# 2017_FDP_PROPULSION.net
KiCad netlist of a schematic drawn in Altium Designer
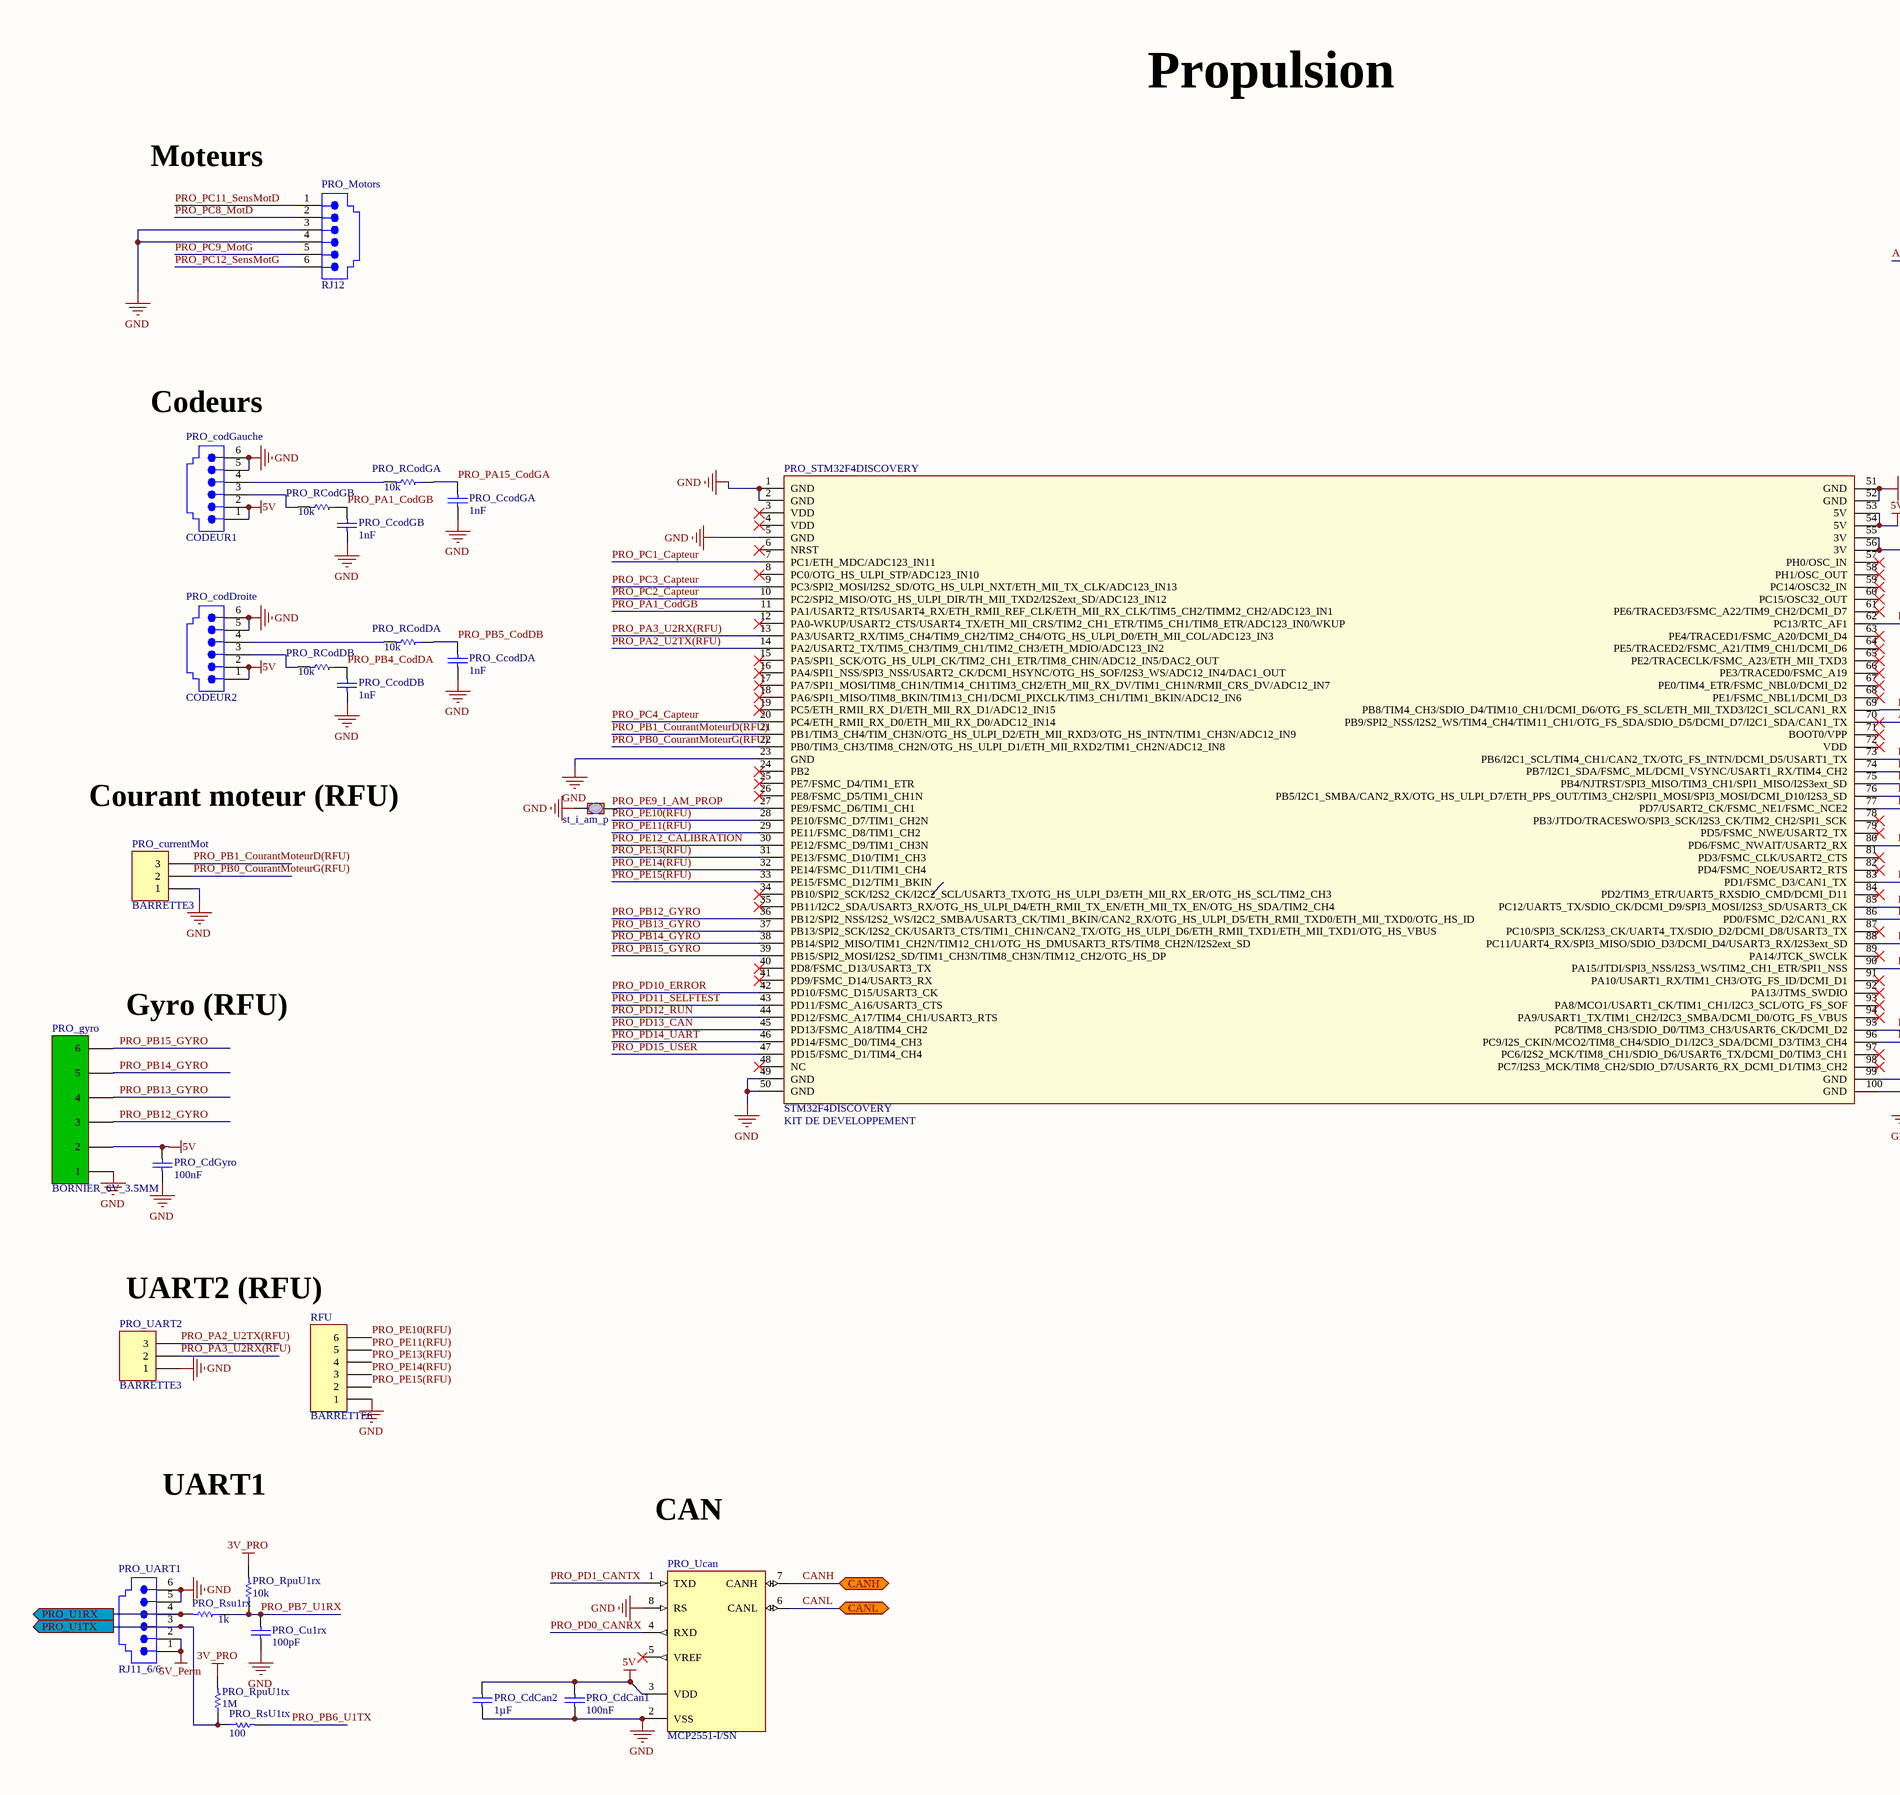
[diagram p0: 2017_FDP_PROPULSION.SchDoc, left]
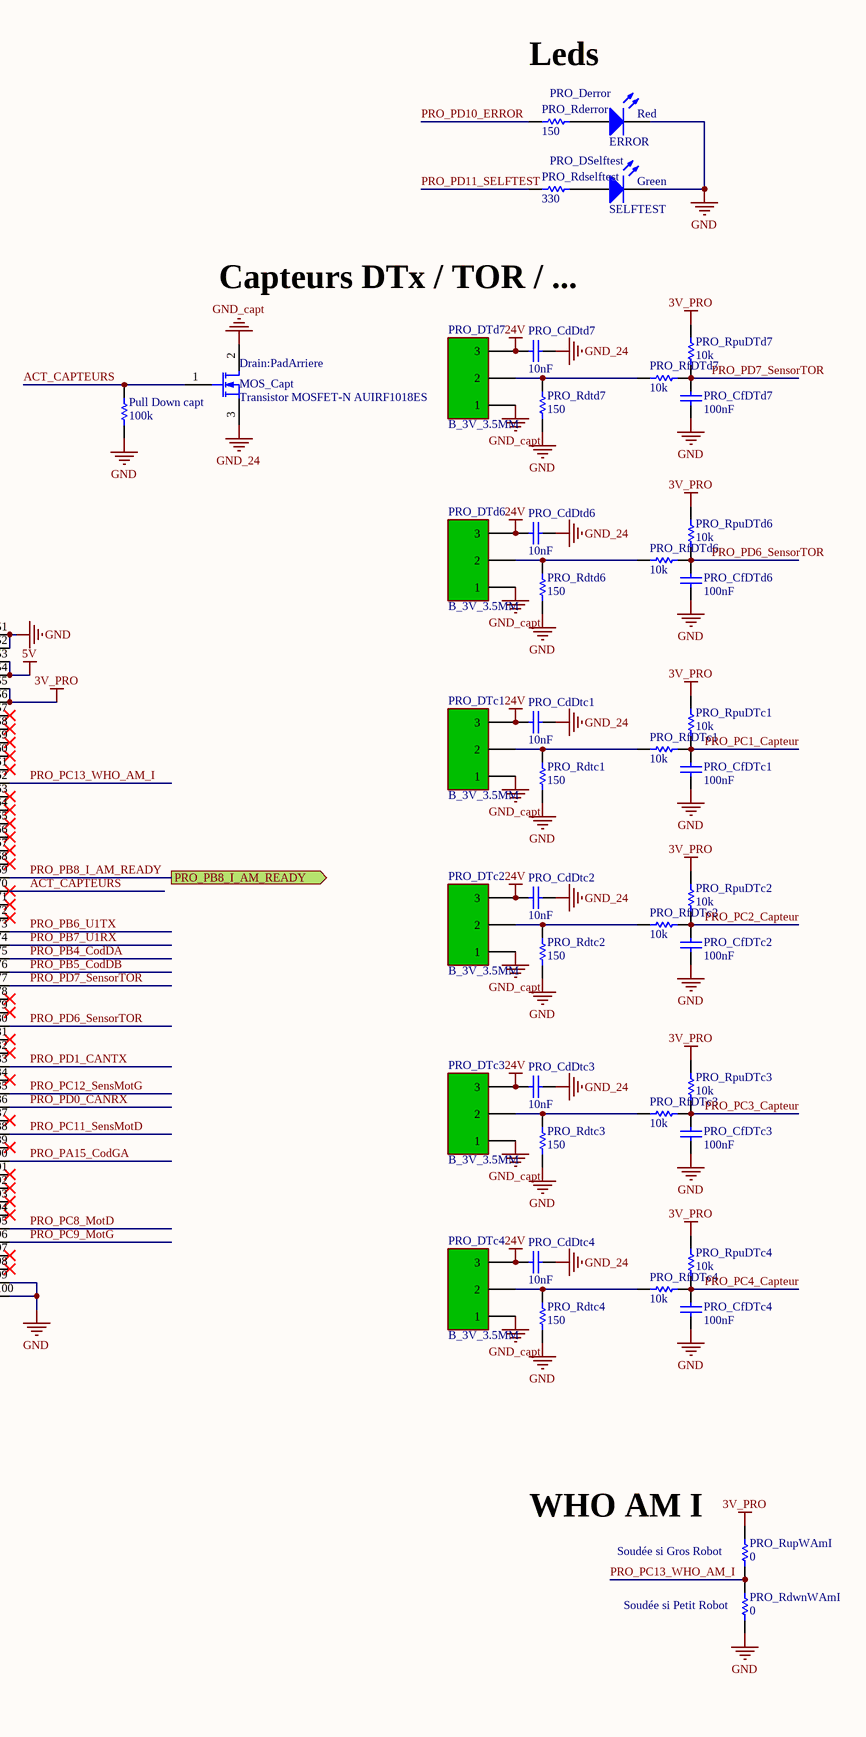
[diagram p1: 2017_FDP_PROPULSION.SchDoc, right]

(export (version "E")
  (design (tool "Eeschema 10.0.6"))
  (components
    (comp (ref "MOS_Capt")
      (value "Transistor MOSFET-N AUIRF1018ES")
      (footprint "D2PAK_GROS_PAD")
      (description "N-Channel MOSFET")
      (fields (field (name "PUBLISHER") "Altium Limited"))
      (libsource (lib "_ROBOT") (part "Transistor MOSFET-N AUIRF1018ES"))
    )
    (comp (ref "PRO_CcodDA")
      (value "1nF")
      (footprint "C0805_N")
      (description "Capacitor")
      (fields (field (name "PUBLISHER") "Altium Limited"))
      (libsource (lib "_ROBOT") (part "Condensateur"))
    )
    (comp (ref "PRO_CcodDB")
      (value "1nF")
      (footprint "C0805_N")
      (description "Capacitor")
      (fields (field (name "PUBLISHER") "Altium Limited"))
      (libsource (lib "_ROBOT") (part "Condensateur"))
    )
    (comp (ref "PRO_CcodGA")
      (value "1nF")
      (footprint "C0805_N")
      (description "Capacitor")
      (fields (field (name "PUBLISHER") "Altium Limited"))
      (libsource (lib "_ROBOT") (part "Condensateur"))
    )
    (comp (ref "PRO_CcodGB")
      (value "1nF")
      (footprint "C0805_N")
      (description "Capacitor")
      (fields (field (name "PUBLISHER") "Altium Limited"))
      (libsource (lib "_ROBOT") (part "Condensateur"))
    )
    (comp (ref "PRO_CdCan1")
      (value "100nF")
      (footprint "C0805_N")
      (description "Capacitor")
      (fields (field (name "PUBLISHER") "Altium Limited"))
      (libsource (lib "_ROBOT") (part "Condensateur"))
    )
    (comp (ref "PRO_CdCan2")
      (value "1µF")
      (footprint "C0805_N")
      (description "Capacitor")
      (fields (field (name "PUBLISHER") "Altium Limited"))
      (libsource (lib "_ROBOT") (part "Condensateur"))
    )
    (comp (ref "PRO_CdDtc1")
      (value "10nF")
      (footprint "C0805_N")
      (description "Capacitor")
      (fields (field (name "PUBLISHER") "Altium Limited"))
      (libsource (lib "_ROBOT") (part "Condensateur"))
    )
    (comp (ref "PRO_CdDtc2")
      (value "10nF")
      (footprint "C0805_N")
      (description "Capacitor")
      (fields (field (name "PUBLISHER") "Altium Limited"))
      (libsource (lib "_ROBOT") (part "Condensateur"))
    )
    (comp (ref "PRO_CdDtc3")
      (value "10nF")
      (footprint "C0805_N")
      (description "Capacitor")
      (fields (field (name "PUBLISHER") "Altium Limited"))
      (libsource (lib "_ROBOT") (part "Condensateur"))
    )
    (comp (ref "PRO_CdDtc4")
      (value "10nF")
      (footprint "C0805_N")
      (description "Capacitor")
      (fields (field (name "PUBLISHER") "Altium Limited"))
      (libsource (lib "_ROBOT") (part "Condensateur"))
    )
    (comp (ref "PRO_CdDtd6")
      (value "10nF")
      (footprint "C0805_N")
      (description "Capacitor")
      (fields (field (name "PUBLISHER") "Altium Limited"))
      (libsource (lib "_ROBOT") (part "Condensateur"))
    )
    (comp (ref "PRO_CdDtd7")
      (value "10nF")
      (footprint "C0805_N")
      (description "Capacitor")
      (fields (field (name "PUBLISHER") "Altium Limited"))
      (libsource (lib "_ROBOT") (part "Condensateur"))
    )
    (comp (ref "PRO_CdGyro")
      (value "100nF")
      (footprint "C0805_N")
      (description "Capacitor")
      (fields (field (name "PUBLISHER") "Altium Limited"))
      (libsource (lib "_ROBOT") (part "Condensateur"))
    )
    (comp (ref "PRO_CfDTc1")
      (value "100nF")
      (footprint "C0805_N")
      (description "Capacitor")
      (fields (field (name "PUBLISHER") "Altium Limited"))
      (libsource (lib "_ROBOT") (part "Condensateur"))
    )
    (comp (ref "PRO_CfDTc2")
      (value "100nF")
      (footprint "C0805_N")
      (description "Capacitor")
      (fields (field (name "PUBLISHER") "Altium Limited"))
      (libsource (lib "_ROBOT") (part "Condensateur"))
    )
    (comp (ref "PRO_CfDTc3")
      (value "100nF")
      (footprint "C0805_N")
      (description "Capacitor")
      (fields (field (name "PUBLISHER") "Altium Limited"))
      (libsource (lib "_ROBOT") (part "Condensateur"))
    )
    (comp (ref "PRO_CfDTc4")
      (value "100nF")
      (footprint "C0805_N")
      (description "Capacitor")
      (fields (field (name "PUBLISHER") "Altium Limited"))
      (libsource (lib "_ROBOT") (part "Condensateur"))
    )
    (comp (ref "PRO_CfDTd6")
      (value "100nF")
      (footprint "C0805_N")
      (description "Capacitor")
      (fields (field (name "PUBLISHER") "Altium Limited"))
      (libsource (lib "_ROBOT") (part "Condensateur"))
    )
    (comp (ref "PRO_CfDTd7")
      (value "100nF")
      (footprint "C0805_N")
      (description "Capacitor")
      (fields (field (name "PUBLISHER") "Altium Limited"))
      (libsource (lib "_ROBOT") (part "Condensateur"))
    )
    (comp (ref "PRO_codDroite")
      (value "CODEUR2")
      (footprint "RJ11_6/6 - droit")
      (description "Right Angle, Standard Profile, Offset Latch DECconnect, Flangeless PCB Jack")
      (fields (field (name "PUBLISHER") "Altium Limited"))
      (libsource (lib "miniprojet") (part "RJ11_6/6"))
    )
    (comp (ref "PRO_codGauche")
      (value "CODEUR1")
      (footprint "RJ11_6/6 - droit")
      (description "Right Angle, Standard Profile, Offset Latch DECconnect, Flangeless PCB Jack")
      (fields (field (name "PUBLISHER") "Altium Limited"))
      (libsource (lib "miniprojet") (part "RJ11_6/6"))
    )
    (comp (ref "PRO_Cu1rx")
      (value "100pF")
      (footprint "C0805_N")
      (description "Capacitor")
      (fields (field (name "PUBLISHER") "Altium Limited"))
      (libsource (lib "_ROBOT") (part "Condensateur"))
    )
    (comp (ref "PRO_currentMot")
      (value "BARRETTE3")
      (footprint "HE14_3")
      (description "Header, 3-Pin")
      (fields (field (name "PUBLISHER") "Altium Limited"))
      (libsource (lib "Connecteur") (part "BARRETTE3"))
    )
    (comp (ref "PRO_Derror")
      (value "ERROR")
      (footprint "LED_0805")
      (description "Typical LED")
      (fields (field (name "PUBLISHER") "Altium Limited"))
      (libsource (lib "_ROBOT") (part "LED"))
    )
    (comp (ref "PRO_DSelftest")
      (value "SELFTEST")
      (footprint "LED_0805")
      (description "Typical LED")
      (fields (field (name "PUBLISHER") "Altium Limited"))
      (libsource (lib "_ROBOT") (part "LED"))
    )
    (comp (ref "PRO_DTc1")
      (value "B_3V_3.5MM")
      (footprint "BORNIER_3V_3.5MM")
      (libsource (lib "Connecteur") (part "BORNIER_3V_3.5MM"))
    )
    (comp (ref "PRO_DTc2")
      (value "B_3V_3.5MM")
      (footprint "BORNIER_3V_3.5MM")
      (libsource (lib "Connecteur") (part "BORNIER_3V_3.5MM"))
    )
    (comp (ref "PRO_DTc3")
      (value "B_3V_3.5MM")
      (footprint "BORNIER_3V_3.5MM")
      (libsource (lib "Connecteur") (part "BORNIER_3V_3.5MM"))
    )
    (comp (ref "PRO_DTc4")
      (value "B_3V_3.5MM")
      (footprint "BORNIER_3V_3.5MM")
      (libsource (lib "Connecteur") (part "BORNIER_3V_3.5MM"))
    )
    (comp (ref "PRO_DTd6")
      (value "B_3V_3.5MM")
      (footprint "BORNIER_3V_3.5MM")
      (libsource (lib "Connecteur") (part "BORNIER_3V_3.5MM"))
    )
    (comp (ref "PRO_DTd7")
      (value "B_3V_3.5MM")
      (footprint "BORNIER_3V_3.5MM")
      (libsource (lib "Connecteur") (part "BORNIER_3V_3.5MM"))
    )
    (comp (ref "PRO_gyro")
      (value "BORNIER_6V_3.5MM")
      (footprint "BORNIER_6V_3.5MM")
      (libsource (lib "Connecteur") (part "BORNIER_6V_3.5MM"))
    )
    (comp (ref "PRO_Motors")
      (value "RJ12")
      (footprint "RJ11_6/6 - droit")
      (description "Right Angle, Standard Profile, Offset Latch DECconnect, Flangeless PCB Jack")
      (fields (field (name "PUBLISHER") "Altium Limited"))
      (libsource (lib "Connecteur") (part "RJ11_6/6"))
    )
    (comp (ref "PRO_RCodDA")
      (value "10k")
      (footprint "R1206_N")
      (description "Resistor")
      (fields (field (name "PUBLISHER") "Altium Limited"))
      (libsource (lib "_ROBOT") (part "Resistor"))
    )
    (comp (ref "PRO_RCodDB")
      (value "10k")
      (footprint "R1206_N")
      (description "Resistor")
      (fields (field (name "PUBLISHER") "Altium Limited"))
      (libsource (lib "_ROBOT") (part "Resistor"))
    )
    (comp (ref "PRO_RCodGA")
      (value "10k")
      (footprint "R1206_N")
      (description "Resistor")
      (fields (field (name "PUBLISHER") "Altium Limited"))
      (libsource (lib "_ROBOT") (part "Resistor"))
    )
    (comp (ref "PRO_RCodGB")
      (value "10k")
      (footprint "R1206_N")
      (description "Resistor")
      (fields (field (name "PUBLISHER") "Altium Limited"))
      (libsource (lib "_ROBOT") (part "Resistor"))
    )
    (comp (ref "PRO_Rderror")
      (value "150")
      (footprint "R1206_N")
      (description "Resistor")
      (fields (field (name "PUBLISHER") "Altium Limited"))
      (libsource (lib "_ROBOT") (part "Resistor"))
    )
    (comp (ref "PRO_Rdselftest")
      (value "330")
      (footprint "R1206_N")
      (description "Resistor")
      (fields (field (name "PUBLISHER") "Altium Limited"))
      (libsource (lib "_ROBOT") (part "Resistor"))
    )
    (comp (ref "PRO_Rdtc1")
      (value "150")
      (footprint "R1206_N")
      (description "Resistor")
      (fields (field (name "PUBLISHER") "Altium Limited"))
      (libsource (lib "_ROBOT") (part "Resistor"))
    )
    (comp (ref "PRO_Rdtc2")
      (value "150")
      (footprint "R1206_N")
      (description "Resistor")
      (fields (field (name "PUBLISHER") "Altium Limited"))
      (libsource (lib "_ROBOT") (part "Resistor"))
    )
    (comp (ref "PRO_Rdtc3")
      (value "150")
      (footprint "R1206_N")
      (description "Resistor")
      (fields (field (name "PUBLISHER") "Altium Limited"))
      (libsource (lib "_ROBOT") (part "Resistor"))
    )
    (comp (ref "PRO_Rdtc4")
      (value "150")
      (footprint "R1206_N")
      (description "Resistor")
      (fields (field (name "PUBLISHER") "Altium Limited"))
      (libsource (lib "_ROBOT") (part "Resistor"))
    )
    (comp (ref "PRO_Rdtd6")
      (value "150")
      (footprint "R1206_N")
      (description "Resistor")
      (fields (field (name "PUBLISHER") "Altium Limited"))
      (libsource (lib "_ROBOT") (part "Resistor"))
    )
    (comp (ref "PRO_Rdtd7")
      (value "150")
      (footprint "R1206_N")
      (description "Resistor")
      (fields (field (name "PUBLISHER") "Altium Limited"))
      (libsource (lib "_ROBOT") (part "Resistor"))
    )
    (comp (ref "PRO_RdwnWAmI")
      (value "0")
      (footprint "R1206_N")
      (description "Resistor")
      (fields (field (name "PUBLISHER") "Altium Limited"))
      (libsource (lib "_ROBOT") (part "Resistor"))
    )
    (comp (ref "PRO_RfDTc1")
      (value "10k")
      (footprint "R1206_N")
      (description "Resistor")
      (fields (field (name "PUBLISHER") "Altium Limited"))
      (libsource (lib "_ROBOT") (part "Resistor"))
    )
    (comp (ref "PRO_RfDTc2")
      (value "10k")
      (footprint "R1206_N")
      (description "Resistor")
      (fields (field (name "PUBLISHER") "Altium Limited"))
      (libsource (lib "_ROBOT") (part "Resistor"))
    )
    (comp (ref "PRO_RfDTc3")
      (value "10k")
      (footprint "R1206_N")
      (description "Resistor")
      (fields (field (name "PUBLISHER") "Altium Limited"))
      (libsource (lib "_ROBOT") (part "Resistor"))
    )
    (comp (ref "PRO_RfDTc4")
      (value "10k")
      (footprint "R1206_N")
      (description "Resistor")
      (fields (field (name "PUBLISHER") "Altium Limited"))
      (libsource (lib "_ROBOT") (part "Resistor"))
    )
    (comp (ref "PRO_RfDTd6")
      (value "10k")
      (footprint "R1206_N")
      (description "Resistor")
      (fields (field (name "PUBLISHER") "Altium Limited"))
      (libsource (lib "_ROBOT") (part "Resistor"))
    )
    (comp (ref "PRO_RfDTd7")
      (value "10k")
      (footprint "R1206_N")
      (description "Resistor")
      (fields (field (name "PUBLISHER") "Altium Limited"))
      (libsource (lib "_ROBOT") (part "Resistor"))
    )
    (comp (ref "PRO_RpuDTc1")
      (value "10k")
      (footprint "R1206_N")
      (description "Resistor")
      (fields (field (name "PUBLISHER") "Altium Limited"))
      (libsource (lib "_ROBOT") (part "Resistor"))
    )
    (comp (ref "PRO_RpuDTc2")
      (value "10k")
      (footprint "R1206_N")
      (description "Resistor")
      (fields (field (name "PUBLISHER") "Altium Limited"))
      (libsource (lib "_ROBOT") (part "Resistor"))
    )
    (comp (ref "PRO_RpuDTc3")
      (value "10k")
      (footprint "R1206_N")
      (description "Resistor")
      (fields (field (name "PUBLISHER") "Altium Limited"))
      (libsource (lib "_ROBOT") (part "Resistor"))
    )
    (comp (ref "PRO_RpuDTc4")
      (value "10k")
      (footprint "R1206_N")
      (description "Resistor")
      (fields (field (name "PUBLISHER") "Altium Limited"))
      (libsource (lib "_ROBOT") (part "Resistor"))
    )
    (comp (ref "PRO_RpuDTd6")
      (value "10k")
      (footprint "R1206_N")
      (description "Resistor")
      (fields (field (name "PUBLISHER") "Altium Limited"))
      (libsource (lib "_ROBOT") (part "Resistor"))
    )
    (comp (ref "PRO_RpuDTd7")
      (value "10k")
      (footprint "R1206_N")
      (description "Resistor")
      (fields (field (name "PUBLISHER") "Altium Limited"))
      (libsource (lib "_ROBOT") (part "Resistor"))
    )
    (comp (ref "PRO_RpuU1rx")
      (value "10k")
      (footprint "R1206_N")
      (description "Resistor")
      (fields (field (name "PUBLISHER") "Altium Limited"))
      (libsource (lib "_ROBOT") (part "Resistor"))
    )
    (comp (ref "PRO_RpuU1tx")
      (value "1M")
      (footprint "R1206_N")
      (description "Resistor")
      (fields (field (name "PUBLISHER") "Altium Limited"))
      (libsource (lib "_ROBOT") (part "Resistor"))
    )
    (comp (ref "PRO_Rsu1rx")
      (value "1k")
      (footprint "R1206_N")
      (description "Resistor")
      (fields (field (name "PUBLISHER") "Altium Limited"))
      (libsource (lib "_ROBOT") (part "Resistor"))
    )
    (comp (ref "PRO_RsU1tx")
      (value "100")
      (footprint "R1206_N")
      (description "Resistor")
      (fields (field (name "PUBLISHER") "Altium Limited"))
      (libsource (lib "_ROBOT") (part "Resistor"))
    )
    (comp (ref "PRO_RupWAmI")
      (value "0")
      (footprint "R1206_N")
      (description "Resistor")
      (fields (field (name "PUBLISHER") "Altium Limited"))
      (libsource (lib "_ROBOT") (part "Resistor"))
    )
    (comp (ref "PRO_STM32F4DISCOVERY")
      (value "STM32F4DISCOVERY")
      (footprint "STM32_F4DISCOVERY")
      (description "KIT DE DEVELOPPEMENT POUR MICROCONTROLEUR STM32F407VGT6")
      (fields (field (name "TYPE") "KIT DE DEVELOPPEMENT"))
      (libsource (lib "circuits integres") (part "STM32F4DISCOVERY"))
    )
    (comp (ref "PRO_UART1")
      (value "RJ11_6/6")
      (footprint "RJ11_6/6 - droit")
      (description "Right Angle, Standard Profile, Offset Latch DECconnect, Flangeless PCB Jack")
      (fields (field (name "PUBLISHER") "Altium Limited"))
      (libsource (lib "Connecteur") (part "RJ11_6/6"))
    )
    (comp (ref "PRO_UART2")
      (value "BARRETTE3")
      (footprint "HE14_3")
      (description "Header, 3-Pin")
      (fields (field (name "PUBLISHER") "Altium Limited"))
      (libsource (lib "Connecteur") (part "BARRETTE3"))
    )
    (comp (ref "PRO_Ucan")
      (value "MCP2551-I/SN")
      (footprint "SO8_N")
      (description "High-Speed CAN Transceiver, 8-Pin SOIC, Industrial Temperature")
      (fields (field (name "PUBLISHER") "Damien Guitton"))
      (libsource (lib "Circuit intégré") (part "MCP2551-I/SN"))
    )
    (comp (ref "Pull Down capt")
      (value "100k")
      (footprint "R1206_N")
      (description "Resistor")
      (fields (field (name "PUBLISHER") "Altium Limited"))
      (libsource (lib "_ROBOT") (part "Resistor"))
    )
    (comp (ref "RFU")
      (value "BARRETTE6")
      (footprint "HE14_6")
      (description "Header, 6-Pin")
      (fields (field (name "PUBLISHER") "Altium Limited"))
      (libsource (lib "Connecteur") (part "BARRETTE6"))
    )
    (comp (ref "st_i_am_p")
      (value "Goutte Strap_2")
      (footprint "Goutte Strap_2 Pads_Clearance 0.254mm")
      (fields (field (name "PUBLISHER") "Damien Guitton"))
      (libsource (lib "DG_Connecteur") (part "Goutte Strap_2"))
    )
  )
  (nets
    (net (code "1") (name "/ACT_CAPTEURS") (class "Default")
      (node (ref "MOS_Capt") (pin "1") (pinfunction "G_1") (pintype "passive"))
      (node (ref "PRO_STM32F4DISCOVERY") (pin "70") (pinfunction "PB9/SPI2_NSS/I2S2_WS/TIM4_CH4/TIM11_CH1/OTG_FS_SDA/SDIO_D5/DCMI_D7/I2C1_SDA/CAN1_TX_70") (pintype "passive"))
      (node (ref "Pull Down capt") (pin "2") (pinfunction "2_2") (pintype "passive"))
    )
    (net (code "2") (name "/CANH") (class "Default")
      (node (ref "PRO_Ucan") (pin "7") (pinfunction "CANH_7") (pintype "bidirectional"))
    )
    (net (code "3") (name "/CANL") (class "Default")
      (node (ref "PRO_Ucan") (pin "6") (pinfunction "CANL_6") (pintype "bidirectional"))
    )
    (net (code "4") (name "/PRO_PA1_CodGB") (class "Default")
      (node (ref "PRO_CcodGB") (pin "2") (pinfunction "2_2") (pintype "passive"))
      (node (ref "PRO_RCodGB") (pin "1") (pinfunction "1_1") (pintype "passive"))
      (node (ref "PRO_STM32F4DISCOVERY") (pin "11") (pinfunction "PA1/USART2_RTS/USART4_RX/ETH_RMII_REF_CLK/ETH_MII_RX_CLK/TIM5_CH2/TIMM2_CH2/ADC123_IN1_11") (pintype "passive"))
    )
    (net (code "5") (name "/PRO_PA2_U2TX(RFU)") (class "Default")
      (node (ref "PRO_STM32F4DISCOVERY") (pin "14") (pinfunction "PA2/USART2_TX/TIM5_CH3/TIM9_CH1/TIM2_CH3/ETH_MDIO/ADC123_IN2_14") (pintype "passive"))
      (node (ref "PRO_UART2") (pin "3") (pinfunction "3_3") (pintype "passive"))
    )
    (net (code "6") (name "/PRO_PA3_U2RX(RFU)") (class "Default")
      (node (ref "PRO_STM32F4DISCOVERY") (pin "13") (pinfunction "PA3/USART2_RX/TIM5_CH4/TIM9_CH2/TIM2_CH4/OTG_HS_ULPI_D0/ETH_MII_COL/ADC123_IN3_13") (pintype "passive"))
      (node (ref "PRO_UART2") (pin "2") (pinfunction "2_2") (pintype "passive"))
    )
    (net (code "7") (name "/PRO_PA15_CodGA") (class "Default")
      (node (ref "PRO_CcodGA") (pin "2") (pinfunction "2_2") (pintype "passive"))
      (node (ref "PRO_RCodGA") (pin "1") (pinfunction "1_1") (pintype "passive"))
      (node (ref "PRO_STM32F4DISCOVERY") (pin "90") (pinfunction "PA15/JTDI/SPI3_NSS/I2S3_WS/TIM2_CH1_ETR/SPI1_NSS_90") (pintype "passive"))
    )
    (net (code "8") (name "/PRO_PB0_CourantMoteurG(RFU)") (class "Default")
      (node (ref "PRO_STM32F4DISCOVERY") (pin "22") (pinfunction "PB0/TIM3_CH3/TIM8_CH2N/OTG_HS_ULPI_D1/ETH_MII_RXD2/TIM1_CH2N/ADC12_IN8_22") (pintype "passive"))
      (node (ref "PRO_currentMot") (pin "2") (pinfunction "2_2") (pintype "passive"))
    )
    (net (code "9") (name "/PRO_PB1_CourantMoteurD(RFU)") (class "Default")
      (node (ref "PRO_STM32F4DISCOVERY") (pin "21") (pinfunction "PB1/TIM3_CH4/TIM_CH3N/OTG_HS_ULPI_D2/ETH_MII_RXD3/OTG_HS_INTN/TIM1_CH3N/ADC12_IN9_21") (pintype "passive"))
      (node (ref "PRO_currentMot") (pin "3") (pinfunction "3_3") (pintype "passive"))
    )
    (net (code "10") (name "/PRO_PB4_CodDA") (class "Default")
      (node (ref "PRO_CcodDB") (pin "2") (pinfunction "2_2") (pintype "passive"))
      (node (ref "PRO_RCodDB") (pin "1") (pinfunction "1_1") (pintype "passive"))
      (node (ref "PRO_STM32F4DISCOVERY") (pin "75") (pinfunction "PB4/NJTRST/SPI3_MISO/TIM3_CH1/SPI1_MISO/I2S3ext_SD_75") (pintype "passive"))
    )
    (net (code "11") (name "/PRO_PB5_CodDB") (class "Default")
      (node (ref "PRO_CcodDA") (pin "2") (pinfunction "2_2") (pintype "passive"))
      (node (ref "PRO_RCodDA") (pin "1") (pinfunction "1_1") (pintype "passive"))
      (node (ref "PRO_STM32F4DISCOVERY") (pin "76") (pinfunction "PB5/I2C1_SMBA/CAN2_RX/OTG_HS_ULPI_D7/ETH_PPS_OUT/TIM3_CH2/SPI1_MOSI/SPI3_MOSI/DCMI_D10/I2S3_SD_76") (pintype "passive"))
    )
    (net (code "12") (name "/PRO_PB6_U1TX") (class "Default")
      (node (ref "PRO_RsU1tx") (pin "2") (pinfunction "2_2") (pintype "passive"))
      (node (ref "PRO_STM32F4DISCOVERY") (pin "73") (pinfunction "PB6/I2C1_SCL/TIM4_CH1/CAN2_TX/OTG_FS_INTN/DCMI_D5/USART1_TX_73") (pintype "passive"))
    )
    (net (code "13") (name "/PRO_PB7_U1RX") (class "Default")
      (node (ref "PRO_Cu1rx") (pin "2") (pinfunction "2_2") (pintype "passive"))
      (node (ref "PRO_RpuU1rx") (pin "1") (pinfunction "1_1") (pintype "passive"))
      (node (ref "PRO_Rsu1rx") (pin "1") (pinfunction "1_1") (pintype "passive"))
      (node (ref "PRO_STM32F4DISCOVERY") (pin "74") (pinfunction "PB7/I2C1_SDA/FSMC_ML/DCMI_VSYNC/USART1_RX/TIM4_CH2_74") (pintype "passive"))
    )
    (net (code "14") (name "/PRO_PB8_I_AM_READY") (class "Default")
      (node (ref "PRO_STM32F4DISCOVERY") (pin "69") (pinfunction "PB8/TIM4_CH3/SDIO_D4/TIM10_CH1/DCMI_D6/OTG_FS_SCL/ETH_MII_TXD3/I2C1_SCL/CAN1_RX_69") (pintype "passive"))
    )
    (net (code "15") (name "/PRO_PB12_GYRO") (class "Default")
      (node (ref "PRO_STM32F4DISCOVERY") (pin "36") (pinfunction "PB12/SPI2_NSS/I2S2_WS/I2C2_SMBA/USART3_CK/TIM1_BKIN/CAN2_RX/OTG_HS_ULPI_D5/ETH_RMII_TXD0/ETH_MII_TXD0/OTG_HS_ID_36") (pintype "passive"))
      (node (ref "PRO_gyro") (pin "3") (pinfunction "3_3") (pintype "passive"))
    )
    (net (code "16") (name "/PRO_PB13_GYRO") (class "Default")
      (node (ref "PRO_STM32F4DISCOVERY") (pin "37") (pinfunction "PB13/SPI2_SCK/I2S2_CK/USART3_CTS/TIM1_CH1N/CAN2_TX/OTG_HS_ULPI_D6/ETH_RMII_TXD1/ETH_MII_TXD1/OTG_HS_VBUS_37") (pintype "passive"))
      (node (ref "PRO_gyro") (pin "4") (pinfunction "4_4") (pintype "passive"))
    )
    (net (code "17") (name "/PRO_PB14_GYRO") (class "Default")
      (node (ref "PRO_STM32F4DISCOVERY") (pin "38") (pinfunction "PB14/SPI2_MISO/TIM1_CH2N/TIM12_CH1/OTG_HS_DMUSART3_RTS/TIM8_CH2N/I2S2ext_SD_38") (pintype "passive"))
      (node (ref "PRO_gyro") (pin "5") (pinfunction "5_5") (pintype "passive"))
    )
    (net (code "18") (name "/PRO_PB15_GYRO") (class "Default")
      (node (ref "PRO_STM32F4DISCOVERY") (pin "39") (pinfunction "PB15/SPI2_MOSI/I2S2_SD/TIM1_CH3N/TIM8_CH3N/TIM12_CH2/OTG_HS_DP_39") (pintype "passive"))
      (node (ref "PRO_gyro") (pin "6") (pinfunction "6_6") (pintype "passive"))
    )
    (net (code "19") (name "/PRO_PC1_Capteur") (class "Default")
      (node (ref "PRO_CfDTc1") (pin "2") (pinfunction "2_2") (pintype "passive"))
      (node (ref "PRO_RfDTc1") (pin "2") (pinfunction "2_2") (pintype "passive"))
      (node (ref "PRO_RpuDTc1") (pin "1") (pinfunction "1_1") (pintype "passive"))
      (node (ref "PRO_STM32F4DISCOVERY") (pin "7") (pinfunction "PC1/ETH_MDC/ADC123_IN11_7") (pintype "passive"))
    )
    (net (code "20") (name "/PRO_PC2_Capteur") (class "Default")
      (node (ref "PRO_CfDTc2") (pin "2") (pinfunction "2_2") (pintype "passive"))
      (node (ref "PRO_RfDTc2") (pin "2") (pinfunction "2_2") (pintype "passive"))
      (node (ref "PRO_RpuDTc2") (pin "1") (pinfunction "1_1") (pintype "passive"))
      (node (ref "PRO_STM32F4DISCOVERY") (pin "10") (pinfunction "PC2/SPI2_MISO/OTG_HS_ULPI_DIR/TH_MII_TXD2/I2S2ext_SD/ADC123_IN12_10") (pintype "passive"))
    )
    (net (code "21") (name "/PRO_PC3_Capteur") (class "Default")
      (node (ref "PRO_CfDTc3") (pin "2") (pinfunction "2_2") (pintype "passive"))
      (node (ref "PRO_RfDTc3") (pin "2") (pinfunction "2_2") (pintype "passive"))
      (node (ref "PRO_RpuDTc3") (pin "1") (pinfunction "1_1") (pintype "passive"))
      (node (ref "PRO_STM32F4DISCOVERY") (pin "9") (pinfunction "PC3/SPI2_MOSI/I2S2_SD/OTG_HS_ULPI_NXT/ETH_MII_TX_CLK/ADC123_IN13_9") (pintype "passive"))
    )
    (net (code "22") (name "/PRO_PC4_Capteur") (class "Default")
      (node (ref "PRO_CfDTc4") (pin "2") (pinfunction "2_2") (pintype "passive"))
      (node (ref "PRO_RfDTc4") (pin "2") (pinfunction "2_2") (pintype "passive"))
      (node (ref "PRO_RpuDTc4") (pin "1") (pinfunction "1_1") (pintype "passive"))
      (node (ref "PRO_STM32F4DISCOVERY") (pin "20") (pinfunction "PC4/ETH_RMII_RX_D0/ETH_MII_RX_D0/ADC12_IN14_20") (pintype "passive"))
    )
    (net (code "23") (name "/PRO_PC8_MotD") (class "Default")
      (node (ref "PRO_Motors") (pin "2") (pinfunction "2_2") (pintype "passive"))
      (node (ref "PRO_STM32F4DISCOVERY") (pin "95") (pinfunction "PC8/TIM8_CH3/SDIO_D0/TIM3_CH3/USART6_CK/DCMI_D2_95") (pintype "passive"))
    )
    (net (code "24") (name "/PRO_PC9_MotG") (class "Default")
      (node (ref "PRO_Motors") (pin "5") (pinfunction "5_5") (pintype "passive"))
      (node (ref "PRO_STM32F4DISCOVERY") (pin "96") (pinfunction "PC9/I2S_CKIN/MCO2/TIM8_CH4/SDIO_D1/I2C3_SDA/DCMI_D3/TIM3_CH4_96") (pintype "passive"))
    )
    (net (code "25") (name "/PRO_PC11_SensMotD") (class "Default")
      (node (ref "PRO_Motors") (pin "1") (pinfunction "1_1") (pintype "passive"))
      (node (ref "PRO_STM32F4DISCOVERY") (pin "88") (pinfunction "PC11/UART4_RX/SPI3_MISO/SDIO_D3/DCMI_D4/USART3_RX/I2S3ext_SD_88") (pintype "passive"))
    )
    (net (code "26") (name "/PRO_PC12_SensMotG") (class "Default")
      (node (ref "PRO_Motors") (pin "6") (pinfunction "6_6") (pintype "passive"))
      (node (ref "PRO_STM32F4DISCOVERY") (pin "85") (pinfunction "PC12/UART5_TX/SDIO_CK/DCMI_D9/SPI3_MOSI/I2S3_SD/USART3_CK_85") (pintype "passive"))
    )
    (net (code "27") (name "/PRO_PC13_WHO_AM_I") (class "Default")
      (node (ref "PRO_RdwnWAmI") (pin "2") (pinfunction "2_2") (pintype "passive"))
      (node (ref "PRO_RupWAmI") (pin "1") (pinfunction "1_1") (pintype "passive"))
      (node (ref "PRO_STM32F4DISCOVERY") (pin "62") (pinfunction "PC13/RTC_AF1_62") (pintype "passive"))
    )
    (net (code "28") (name "/PRO_PD0_CANRX") (class "Default")
      (node (ref "PRO_STM32F4DISCOVERY") (pin "86") (pinfunction "PD0/FSMC_D2/CAN1_RX_86") (pintype "passive"))
      (node (ref "PRO_Ucan") (pin "4") (pinfunction "RXD_4") (pintype "output"))
    )
    (net (code "29") (name "/PRO_PD1_CANTX") (class "Default")
      (node (ref "PRO_STM32F4DISCOVERY") (pin "83") (pinfunction "PD1/FSMC_D3/CAN1_TX_83") (pintype "passive"))
      (node (ref "PRO_Ucan") (pin "1") (pinfunction "TXD_1") (pintype "input"))
    )
    (net (code "30") (name "/PRO_PD6_SensorTOR") (class "Default")
      (node (ref "PRO_CfDTd6") (pin "2") (pinfunction "2_2") (pintype "passive"))
      (node (ref "PRO_RfDTd6") (pin "2") (pinfunction "2_2") (pintype "passive"))
      (node (ref "PRO_RpuDTd6") (pin "1") (pinfunction "1_1") (pintype "passive"))
      (node (ref "PRO_STM32F4DISCOVERY") (pin "80") (pinfunction "PD6/FSMC_NWAIT/USART2_RX_80") (pintype "passive"))
    )
    (net (code "31") (name "/PRO_PD7_SensorTOR") (class "Default")
      (node (ref "PRO_CfDTd7") (pin "2") (pinfunction "2_2") (pintype "passive"))
      (node (ref "PRO_RfDTd7") (pin "2") (pinfunction "2_2") (pintype "passive"))
      (node (ref "PRO_RpuDTd7") (pin "1") (pinfunction "1_1") (pintype "passive"))
      (node (ref "PRO_STM32F4DISCOVERY") (pin "77") (pinfunction "PD7/USART2_CK/FSMC_NE1/FSMC_NCE2_77") (pintype "passive"))
    )
    (net (code "32") (name "/PRO_PD10_ERROR") (class "Default")
      (node (ref "PRO_Rderror") (pin "1") (pinfunction "1_1") (pintype "passive"))
      (node (ref "PRO_STM32F4DISCOVERY") (pin "42") (pinfunction "PD10/FSMC_D15/USART3_CK_42") (pintype "passive"))
    )
    (net (code "33") (name "/PRO_PD11_SELFTEST") (class "Default")
      (node (ref "PRO_Rdselftest") (pin "1") (pinfunction "1_1") (pintype "passive"))
      (node (ref "PRO_STM32F4DISCOVERY") (pin "43") (pinfunction "PD11/FSMC_A16/USART3_CTS_43") (pintype "passive"))
    )
    (net (code "34") (name "/PRO_PD12_RUN") (class "Default")
      (node (ref "PRO_STM32F4DISCOVERY") (pin "44") (pinfunction "PD12/FSMC_A17/TIM4_CH1/USART3_RTS_44") (pintype "passive"))
    )
    (net (code "35") (name "/PRO_PD13_CAN") (class "Default")
      (node (ref "PRO_STM32F4DISCOVERY") (pin "45") (pinfunction "PD13/FSMC_A18/TIM4_CH2_45") (pintype "passive"))
    )
    (net (code "36") (name "/PRO_PD14_UART") (class "Default")
      (node (ref "PRO_STM32F4DISCOVERY") (pin "46") (pinfunction "PD14/FSMC_D0/TIM4_CH3_46") (pintype "passive"))
    )
    (net (code "37") (name "/PRO_PD15_USER") (class "Default")
      (node (ref "PRO_STM32F4DISCOVERY") (pin "47") (pinfunction "PD15/FSMC_D1/TIM4_CH4_47") (pintype "passive"))
    )
    (net (code "39") (name "/PRO_PE10(RFU)") (class "Default")
      (node (ref "PRO_STM32F4DISCOVERY") (pin "28") (pinfunction "PE10/FSMC_D7/TIM1_CH2N_28") (pintype "passive"))
      (node (ref "RFU") (pin "6") (pinfunction "6_6") (pintype "passive"))
    )
    (net (code "40") (name "/PRO_PE11(RFU)") (class "Default")
      (node (ref "PRO_STM32F4DISCOVERY") (pin "29") (pinfunction "PE11/FSMC_D8/TIM1_CH2_29") (pintype "passive"))
      (node (ref "RFU") (pin "5") (pinfunction "5_5") (pintype "passive"))
    )
    (net (code "41") (name "/PRO_PE12_CALIBRATION") (class "Default")
      (node (ref "PRO_STM32F4DISCOVERY") (pin "30") (pinfunction "PE12/FSMC_D9/TIM1_CH3N_30") (pintype "passive"))
    )
    (net (code "42") (name "/PRO_PE13(RFU)") (class "Default")
      (node (ref "PRO_STM32F4DISCOVERY") (pin "31") (pinfunction "PE13/FSMC_D10/TIM1_CH3_31") (pintype "passive"))
      (node (ref "RFU") (pin "4") (pinfunction "4_4") (pintype "passive"))
    )
    (net (code "43") (name "/PRO_PE14(RFU)") (class "Default")
      (node (ref "PRO_STM32F4DISCOVERY") (pin "32") (pinfunction "PE14/FSMC_D11/TIM1_CH4_32") (pintype "passive"))
      (node (ref "RFU") (pin "3") (pinfunction "3_3") (pintype "passive"))
    )
    (net (code "44") (name "/PRO_PE15(RFU)") (class "Default")
      (node (ref "PRO_STM32F4DISCOVERY") (pin "33") (pinfunction "PE15/FSMC_D12/TIM1_BKIN_33") (pintype "passive"))
      (node (ref "RFU") (pin "2") (pinfunction "2_2") (pintype "passive"))
    )
    (net (code "45") (name "/PRO_U1RX") (class "Default")
      (node (ref "PRO_Rsu1rx") (pin "2") (pinfunction "2_2") (pintype "passive"))
      (node (ref "PRO_UART1") (pin "4") (pinfunction "4_4") (pintype "passive"))
    )
    (net (code "46") (name "/PRO_U1TX") (class "Default")
      (node (ref "PRO_RpuU1tx") (pin "1") (pinfunction "1_1") (pintype "passive"))
      (node (ref "PRO_RsU1tx") (pin "1") (pinfunction "1_1") (pintype "passive"))
      (node (ref "PRO_UART1") (pin "3") (pinfunction "3_3") (pintype "passive"))
    )
    (net (code "47") (name "3V_PRO") (class "Default")
      (node (ref "PRO_RpuDTc1") (pin "2") (pinfunction "2_2") (pintype "passive"))
      (node (ref "PRO_RpuDTc2") (pin "2") (pinfunction "2_2") (pintype "passive"))
      (node (ref "PRO_RpuDTc3") (pin "2") (pinfunction "2_2") (pintype "passive"))
      (node (ref "PRO_RpuDTc4") (pin "2") (pinfunction "2_2") (pintype "passive"))
      (node (ref "PRO_RpuDTd6") (pin "2") (pinfunction "2_2") (pintype "passive"))
      (node (ref "PRO_RpuDTd7") (pin "2") (pinfunction "2_2") (pintype "passive"))
      (node (ref "PRO_RpuU1rx") (pin "2") (pinfunction "2_2") (pintype "passive"))
      (node (ref "PRO_RpuU1tx") (pin "2") (pinfunction "2_2") (pintype "passive"))
      (node (ref "PRO_RupWAmI") (pin "2") (pinfunction "2_2") (pintype "passive"))
      (node (ref "PRO_STM32F4DISCOVERY") (pin "55") (pinfunction "3V_55") (pintype "passive"))
      (node (ref "PRO_STM32F4DISCOVERY") (pin "56") (pinfunction "3V_56") (pintype "passive"))
    )
    (net (code "48") (name "5V") (class "Default")
      (node (ref "PRO_CdCan1") (pin "2") (pinfunction "2_2") (pintype "passive"))
      (node (ref "PRO_CdCan2") (pin "2") (pinfunction "2_2") (pintype "passive"))
      (node (ref "PRO_CdGyro") (pin "2") (pinfunction "2_2") (pintype "passive"))
      (node (ref "PRO_STM32F4DISCOVERY") (pin "53") (pinfunction "5V_53") (pintype "passive"))
      (node (ref "PRO_STM32F4DISCOVERY") (pin "54") (pinfunction "5V_54") (pintype "passive"))
      (node (ref "PRO_Ucan") (pin "3") (pinfunction "VDD_3") (pintype "power_in"))
      (node (ref "PRO_codDroite") (pin "1") (pinfunction "1_1") (pintype "passive"))
      (node (ref "PRO_codDroite") (pin "2") (pinfunction "2_2") (pintype "passive"))
      (node (ref "PRO_codGauche") (pin "1") (pinfunction "1_1") (pintype "passive"))
      (node (ref "PRO_codGauche") (pin "2") (pinfunction "2_2") (pintype "passive"))
      (node (ref "PRO_gyro") (pin "2") (pinfunction "2_2") (pintype "passive"))
    )
    (net (code "49") (name "5V_Perm") (class "Default")
      (node (ref "PRO_UART1") (pin "1") (pinfunction "1_1") (pintype "passive"))
      (node (ref "PRO_UART1") (pin "2") (pinfunction "2_2") (pintype "passive"))
    )
    (net (code "50") (name "24V") (class "Default")
      (node (ref "PRO_CdDtc1") (pin "2") (pinfunction "2_2") (pintype "passive"))
      (node (ref "PRO_CdDtc2") (pin "2") (pinfunction "2_2") (pintype "passive"))
      (node (ref "PRO_CdDtc3") (pin "2") (pinfunction "2_2") (pintype "passive"))
      (node (ref "PRO_CdDtc4") (pin "2") (pinfunction "2_2") (pintype "passive"))
      (node (ref "PRO_CdDtd6") (pin "2") (pinfunction "2_2") (pintype "passive"))
      (node (ref "PRO_CdDtd7") (pin "2") (pinfunction "2_2") (pintype "passive"))
      (node (ref "PRO_DTc1") (pin "3") (pinfunction "3_3") (pintype "passive"))
      (node (ref "PRO_DTc2") (pin "3") (pinfunction "3_3") (pintype "passive"))
      (node (ref "PRO_DTc3") (pin "3") (pinfunction "3_3") (pintype "passive"))
      (node (ref "PRO_DTc4") (pin "3") (pinfunction "3_3") (pintype "passive"))
      (node (ref "PRO_DTd6") (pin "3") (pinfunction "3_3") (pintype "passive"))
      (node (ref "PRO_DTd7") (pin "3") (pinfunction "3_3") (pintype "passive"))
    )
    (net (code "51") (name "GND") (class "Default")
      (node (ref "PRO_CcodDA") (pin "1") (pinfunction "1_1") (pintype "passive"))
      (node (ref "PRO_CcodDB") (pin "1") (pinfunction "1_1") (pintype "passive"))
      (node (ref "PRO_CcodGA") (pin "1") (pinfunction "1_1") (pintype "passive"))
      (node (ref "PRO_CcodGB") (pin "1") (pinfunction "1_1") (pintype "passive"))
      (node (ref "PRO_CdCan1") (pin "1") (pinfunction "1_1") (pintype "passive"))
      (node (ref "PRO_CdCan2") (pin "1") (pinfunction "1_1") (pintype "passive"))
      (node (ref "PRO_CdGyro") (pin "1") (pinfunction "1_1") (pintype "passive"))
      (node (ref "PRO_CfDTc1") (pin "1") (pinfunction "1_1") (pintype "passive"))
      (node (ref "PRO_CfDTc2") (pin "1") (pinfunction "1_1") (pintype "passive"))
      (node (ref "PRO_CfDTc3") (pin "1") (pinfunction "1_1") (pintype "passive"))
      (node (ref "PRO_CfDTc4") (pin "1") (pinfunction "1_1") (pintype "passive"))
      (node (ref "PRO_CfDTd6") (pin "1") (pinfunction "1_1") (pintype "passive"))
      (node (ref "PRO_CfDTd7") (pin "1") (pinfunction "1_1") (pintype "passive"))
      (node (ref "PRO_Cu1rx") (pin "1") (pinfunction "1_1") (pintype "passive"))
      (node (ref "PRO_DSelftest") (pin "2") (pinfunction "K_2") (pintype "passive"))
      (node (ref "PRO_Derror") (pin "2") (pinfunction "K_2") (pintype "passive"))
      (node (ref "PRO_Motors") (pin "3") (pinfunction "3_3") (pintype "passive"))
      (node (ref "PRO_Motors") (pin "4") (pinfunction "4_4") (pintype "passive"))
      (node (ref "PRO_Rdtc1") (pin "1") (pinfunction "1_1") (pintype "passive"))
      (node (ref "PRO_Rdtc2") (pin "1") (pinfunction "1_1") (pintype "passive"))
      (node (ref "PRO_Rdtc3") (pin "1") (pinfunction "1_1") (pintype "passive"))
      (node (ref "PRO_Rdtc4") (pin "1") (pinfunction "1_1") (pintype "passive"))
      (node (ref "PRO_Rdtd6") (pin "1") (pinfunction "1_1") (pintype "passive"))
      (node (ref "PRO_Rdtd7") (pin "1") (pinfunction "1_1") (pintype "passive"))
      (node (ref "PRO_RdwnWAmI") (pin "1") (pinfunction "1_1") (pintype "passive"))
      (node (ref "PRO_STM32F4DISCOVERY") (pin "1") (pinfunction "GND_1") (pintype "passive"))
      (node (ref "PRO_STM32F4DISCOVERY") (pin "100") (pinfunction "GND_100") (pintype "passive"))
      (node (ref "PRO_STM32F4DISCOVERY") (pin "2") (pinfunction "GND_2") (pintype "passive"))
      (node (ref "PRO_STM32F4DISCOVERY") (pin "23") (pinfunction "GND_23") (pintype "passive"))
      (node (ref "PRO_STM32F4DISCOVERY") (pin "49") (pinfunction "GND_49") (pintype "passive"))
      (node (ref "PRO_STM32F4DISCOVERY") (pin "5") (pinfunction "GND_5") (pintype "passive"))
      (node (ref "PRO_STM32F4DISCOVERY") (pin "50") (pinfunction "GND_50") (pintype "passive"))
      (node (ref "PRO_STM32F4DISCOVERY") (pin "51") (pinfunction "GND_51") (pintype "passive"))
      (node (ref "PRO_STM32F4DISCOVERY") (pin "52") (pinfunction "GND_52") (pintype "passive"))
      (node (ref "PRO_STM32F4DISCOVERY") (pin "99") (pinfunction "GND_99") (pintype "passive"))
      (node (ref "PRO_UART1") (pin "5") (pinfunction "5_5") (pintype "passive"))
      (node (ref "PRO_UART1") (pin "6") (pinfunction "6_6") (pintype "passive"))
      (node (ref "PRO_UART2") (pin "1") (pinfunction "1_1") (pintype "passive"))
      (node (ref "PRO_Ucan") (pin "2") (pinfunction "VSS_2") (pintype "power_in"))
      (node (ref "PRO_Ucan") (pin "8") (pinfunction "RS_8") (pintype "input"))
      (node (ref "PRO_codDroite") (pin "5") (pinfunction "5_5") (pintype "passive"))
      (node (ref "PRO_codDroite") (pin "6") (pinfunction "6_6") (pintype "passive"))
      (node (ref "PRO_codGauche") (pin "5") (pinfunction "5_5") (pintype "passive"))
      (node (ref "PRO_codGauche") (pin "6") (pinfunction "6_6") (pintype "passive"))
      (node (ref "PRO_currentMot") (pin "1") (pinfunction "1_1") (pintype "passive"))
      (node (ref "PRO_gyro") (pin "1") (pinfunction "1_1") (pintype "passive"))
      (node (ref "Pull Down capt") (pin "1") (pinfunction "1_1") (pintype "passive"))
      (node (ref "RFU") (pin "1") (pinfunction "1_1") (pintype "passive"))
      (node (ref "st_i_am_p") (pin "1") (pinfunction "1_1") (pintype "passive"))
    )
    (net (code "52") (name "GND_24") (class "Default")
      (node (ref "MOS_Capt") (pin "3") (pinfunction "S_3") (pintype "passive"))
      (node (ref "PRO_CdDtc1") (pin "1") (pinfunction "1_1") (pintype "passive"))
      (node (ref "PRO_CdDtc2") (pin "1") (pinfunction "1_1") (pintype "passive"))
      (node (ref "PRO_CdDtc3") (pin "1") (pinfunction "1_1") (pintype "passive"))
      (node (ref "PRO_CdDtc4") (pin "1") (pinfunction "1_1") (pintype "passive"))
      (node (ref "PRO_CdDtd6") (pin "1") (pinfunction "1_1") (pintype "passive"))
      (node (ref "PRO_CdDtd7") (pin "1") (pinfunction "1_1") (pintype "passive"))
    )
    (net (code "53") (name "GND_capt") (class "Default")
      (node (ref "MOS_Capt") (pin "2") (pinfunction "D_2") (pintype "passive"))
      (node (ref "PRO_DTc1") (pin "1") (pinfunction "1_1") (pintype "passive"))
      (node (ref "PRO_DTc2") (pin "1") (pinfunction "1_1") (pintype "passive"))
      (node (ref "PRO_DTc3") (pin "1") (pinfunction "1_1") (pintype "passive"))
      (node (ref "PRO_DTc4") (pin "1") (pinfunction "1_1") (pintype "passive"))
      (node (ref "PRO_DTd6") (pin "1") (pinfunction "1_1") (pintype "passive"))
      (node (ref "PRO_DTd7") (pin "1") (pinfunction "1_1") (pintype "passive"))
    )
    (net (code "54") (name "Net-(PRO_DSelftest-A)") (class "Default")
      (node (ref "PRO_DSelftest") (pin "1") (pinfunction "A_1") (pintype "passive"))
      (node (ref "PRO_Rdselftest") (pin "2") (pinfunction "2_2") (pintype "passive"))
    )
    (net (code "55") (name "Net-(PRO_DTc1-Pad2)") (class "Default")
      (node (ref "PRO_DTc1") (pin "2") (pinfunction "2_2") (pintype "passive"))
      (node (ref "PRO_Rdtc1") (pin "2") (pinfunction "2_2") (pintype "passive"))
      (node (ref "PRO_RfDTc1") (pin "1") (pinfunction "1_1") (pintype "passive"))
    )
    (net (code "56") (name "Net-(PRO_DTc2-Pad2)") (class "Default")
      (node (ref "PRO_DTc2") (pin "2") (pinfunction "2_2") (pintype "passive"))
      (node (ref "PRO_Rdtc2") (pin "2") (pinfunction "2_2") (pintype "passive"))
      (node (ref "PRO_RfDTc2") (pin "1") (pinfunction "1_1") (pintype "passive"))
    )
    (net (code "57") (name "Net-(PRO_DTc3-Pad2)") (class "Default")
      (node (ref "PRO_DTc3") (pin "2") (pinfunction "2_2") (pintype "passive"))
      (node (ref "PRO_Rdtc3") (pin "2") (pinfunction "2_2") (pintype "passive"))
      (node (ref "PRO_RfDTc3") (pin "1") (pinfunction "1_1") (pintype "passive"))
    )
    (net (code "58") (name "Net-(PRO_DTc4-Pad2)") (class "Default")
      (node (ref "PRO_DTc4") (pin "2") (pinfunction "2_2") (pintype "passive"))
      (node (ref "PRO_Rdtc4") (pin "2") (pinfunction "2_2") (pintype "passive"))
      (node (ref "PRO_RfDTc4") (pin "1") (pinfunction "1_1") (pintype "passive"))
    )
    (net (code "59") (name "Net-(PRO_DTd6-Pad2)") (class "Default")
      (node (ref "PRO_DTd6") (pin "2") (pinfunction "2_2") (pintype "passive"))
      (node (ref "PRO_Rdtd6") (pin "2") (pinfunction "2_2") (pintype "passive"))
      (node (ref "PRO_RfDTd6") (pin "1") (pinfunction "1_1") (pintype "passive"))
    )
    (net (code "60") (name "Net-(PRO_DTd7-Pad2)") (class "Default")
      (node (ref "PRO_DTd7") (pin "2") (pinfunction "2_2") (pintype "passive"))
      (node (ref "PRO_Rdtd7") (pin "2") (pinfunction "2_2") (pintype "passive"))
      (node (ref "PRO_RfDTd7") (pin "1") (pinfunction "1_1") (pintype "passive"))
    )
    (net (code "61") (name "Net-(PRO_Derror-A)") (class "Default")
      (node (ref "PRO_Derror") (pin "1") (pinfunction "A_1") (pintype "passive"))
      (node (ref "PRO_Rderror") (pin "2") (pinfunction "2_2") (pintype "passive"))
    )
    (net (code "62") (name "Net-(PRO_RCodDA-Pad2)") (class "Default")
      (node (ref "PRO_RCodDA") (pin "2") (pinfunction "2_2") (pintype "passive"))
      (node (ref "PRO_codDroite") (pin "4") (pinfunction "4_4") (pintype "passive"))
    )
    (net (code "63") (name "Net-(PRO_RCodDB-Pad2)") (class "Default")
      (node (ref "PRO_RCodDB") (pin "2") (pinfunction "2_2") (pintype "passive"))
      (node (ref "PRO_codDroite") (pin "3") (pinfunction "3_3") (pintype "passive"))
    )
    (net (code "64") (name "Net-(PRO_RCodGA-Pad2)") (class "Default")
      (node (ref "PRO_RCodGA") (pin "2") (pinfunction "2_2") (pintype "passive"))
      (node (ref "PRO_codGauche") (pin "4") (pinfunction "4_4") (pintype "passive"))
    )
    (net (code "65") (name "Net-(PRO_RCodGB-Pad2)") (class "Default")
      (node (ref "PRO_RCodGB") (pin "2") (pinfunction "2_2") (pintype "passive"))
      (node (ref "PRO_codGauche") (pin "3") (pinfunction "3_3") (pintype "passive"))
    )
    (net (code "66") (name "Net-(PRO_STM32F4DISCOVERY-PE9{slash}FSMC_D6{slash}TIM1_CH1)") (class "Default")
      (node (ref "PRO_STM32F4DISCOVERY") (pin "27") (pinfunction "PE9/FSMC_D6/TIM1_CH1_27") (pintype "passive"))
      (node (ref "st_i_am_p") (pin "2") (pinfunction "2_2") (pintype "passive"))
    )
    (net (code "67") (name "unconnected-(PRO_STM32F4DISCOVERY-BOOT0{slash}VPP-Pad71)") (class "Default")
      (node (ref "PRO_STM32F4DISCOVERY") (pin "71") (pinfunction "BOOT0/VPP_71") (pintype "passive+no_connect"))
    )
    (net (code "68") (name "unconnected-(PRO_STM32F4DISCOVERY-NC-Pad48)") (class "Default")
      (node (ref "PRO_STM32F4DISCOVERY") (pin "48") (pinfunction "NC_48") (pintype "passive+no_connect"))
    )
    (net (code "69") (name "unconnected-(PRO_STM32F4DISCOVERY-NRST-Pad6)") (class "Default")
      (node (ref "PRO_STM32F4DISCOVERY") (pin "6") (pinfunction "NRST_6") (pintype "passive+no_connect"))
    )
    (net (code "70") (name "unconnected-(PRO_STM32F4DISCOVERY-PA0-WKUP{slash}USART2_CTS{slash}USART4_TX{slash}ETH_MII_CRS{slash}TIM2_CH1_ETR{slash}TIM5_CH1{slash}TIM8_ETR{slash}ADC123_IN0{slash}WKUP-Pad12)") (class "Default")
      (node (ref "PRO_STM32F4DISCOVERY") (pin "12") (pinfunction "PA0-WKUP/USART2_CTS/USART4_TX/ETH_MII_CRS/TIM2_CH1_ETR/TIM5_CH1/TIM8_ETR/ADC123_IN0/WKUP_12") (pintype "passive+no_connect"))
    )
    (net (code "71") (name "unconnected-(PRO_STM32F4DISCOVERY-PA4{slash}SPI1_NSS{slash}SPI3_NSS{slash}USART2_CK{slash}DCMI_HSYNC{slash}OTG_HS_SOF{slash}I2S3_WS{slash}ADC12_IN4{slash}DAC1_OUT-Pad16)") (class "Default")
      (node (ref "PRO_STM32F4DISCOVERY") (pin "16") (pinfunction "PA4/SPI1_NSS/SPI3_NSS/USART2_CK/DCMI_HSYNC/OTG_HS_SOF/I2S3_WS/ADC12_IN4/DAC1_OUT_16") (pintype "passive+no_connect"))
    )
    (net (code "72") (name "unconnected-(PRO_STM32F4DISCOVERY-PA5{slash}SPI1_SCK{slash}OTG_HS_ULPI_CK{slash}TIM2_CH1_ETR{slash}TIM8_CHIN{slash}ADC12_IN5{slash}DAC2_OUT-Pad15)") (class "Default")
      (node (ref "PRO_STM32F4DISCOVERY") (pin "15") (pinfunction "PA5/SPI1_SCK/OTG_HS_ULPI_CK/TIM2_CH1_ETR/TIM8_CHIN/ADC12_IN5/DAC2_OUT_15") (pintype "passive+no_connect"))
    )
    (net (code "73") (name "unconnected-(PRO_STM32F4DISCOVERY-PA6{slash}SPI1_MISO{slash}TIM8_BKIN{slash}TIM13_CH1{slash}DCMI_PIXCLK{slash}TIM3_CH1{slash}TIM1_BKIN{slash}ADC12_IN6-Pad18)") (class "Default")
      (node (ref "PRO_STM32F4DISCOVERY") (pin "18") (pinfunction "PA6/SPI1_MISO/TIM8_BKIN/TIM13_CH1/DCMI_PIXCLK/TIM3_CH1/TIM1_BKIN/ADC12_IN6_18") (pintype "passive+no_connect"))
    )
    (net (code "74") (name "unconnected-(PRO_STM32F4DISCOVERY-PA7{slash}SPI1_MOSI{slash}TIM8_CH1N{slash}TIM14_CH1TIM3_CH2{slash}ETH_MII_RX_DV{slash}TIM1_CH1N{slash}RMII_CRS_DV{slash}ADC12_IN7-Pad17)") (class "Default")
      (node (ref "PRO_STM32F4DISCOVERY") (pin "17") (pinfunction "PA7/SPI1_MOSI/TIM8_CH1N/TIM14_CH1TIM3_CH2/ETH_MII_RX_DV/TIM1_CH1N/RMII_CRS_DV/ADC12_IN7_17") (pintype "passive+no_connect"))
    )
    (net (code "75") (name "unconnected-(PRO_STM32F4DISCOVERY-PA8{slash}MCO1{slash}USART1_CK{slash}TIM1_CH1{slash}I2C3_SCL{slash}OTG_FS_SOF-Pad93)") (class "Default")
      (node (ref "PRO_STM32F4DISCOVERY") (pin "93") (pinfunction "PA8/MCO1/USART1_CK/TIM1_CH1/I2C3_SCL/OTG_FS_SOF_93") (pintype "passive+no_connect"))
    )
    (net (code "76") (name "unconnected-(PRO_STM32F4DISCOVERY-PA9{slash}USART1_TX{slash}TIM1_CH2{slash}I2C3_SMBA{slash}DCMI_D0{slash}OTG_FS_VBUS-Pad94)") (class "Default")
      (node (ref "PRO_STM32F4DISCOVERY") (pin "94") (pinfunction "PA9/USART1_TX/TIM1_CH2/I2C3_SMBA/DCMI_D0/OTG_FS_VBUS_94") (pintype "passive+no_connect"))
    )
    (net (code "77") (name "unconnected-(PRO_STM32F4DISCOVERY-PA10{slash}USART1_RX{slash}TIM1_CH3{slash}OTG_FS_ID{slash}DCMI_D1-Pad91)") (class "Default")
      (node (ref "PRO_STM32F4DISCOVERY") (pin "91") (pinfunction "PA10/USART1_RX/TIM1_CH3/OTG_FS_ID/DCMI_D1_91") (pintype "passive+no_connect"))
    )
    (net (code "78") (name "unconnected-(PRO_STM32F4DISCOVERY-PA13{slash}JTMS_SWDIO-Pad92)") (class "Default")
      (node (ref "PRO_STM32F4DISCOVERY") (pin "92") (pinfunction "PA13/JTMS_SWDIO_92") (pintype "passive+no_connect"))
    )
    (net (code "79") (name "unconnected-(PRO_STM32F4DISCOVERY-PA14{slash}JTCK_SWCLK-Pad89)") (class "Default")
      (node (ref "PRO_STM32F4DISCOVERY") (pin "89") (pinfunction "PA14/JTCK_SWCLK_89") (pintype "passive+no_connect"))
    )
    (net (code "80") (name "unconnected-(PRO_STM32F4DISCOVERY-PB2-Pad24)") (class "Default")
      (node (ref "PRO_STM32F4DISCOVERY") (pin "24") (pinfunction "PB2_24") (pintype "passive+no_connect"))
    )
    (net (code "81") (name "unconnected-(PRO_STM32F4DISCOVERY-PB3{slash}JTDO{slash}TRACESWO{slash}SPI3_SCK{slash}I2S3_CK{slash}TIM2_CH2{slash}SPI1_SCK-Pad78)") (class "Default")
      (node (ref "PRO_STM32F4DISCOVERY") (pin "78") (pinfunction "PB3/JTDO/TRACESWO/SPI3_SCK/I2S3_CK/TIM2_CH2/SPI1_SCK_78") (pintype "passive+no_connect"))
    )
    (net (code "82") (name "unconnected-(PRO_STM32F4DISCOVERY-PB10{slash}SPI2_SCK{slash}I2S2_CK{slash}I2C2_SCL{slash}USART3_TX{slash}OTG_HS_ULPI_D3{slash}ETH_MII_RX_ER{slash}OTG_HS_SCL{slash}TIM2_CH3-Pad34)") (class "Default")
      (node (ref "PRO_STM32F4DISCOVERY") (pin "34") (pinfunction "PB10/SPI2_SCK/I2S2_CK/I2C2_SCL/USART3_TX/OTG_HS_ULPI_D3/ETH_MII_RX_ER/OTG_HS_SCL/TIM2_CH3_34") (pintype "passive+no_connect"))
    )
    (net (code "83") (name "unconnected-(PRO_STM32F4DISCOVERY-PB11{slash}I2C2_SDA{slash}USART3_RX{slash}OTG_HS_ULPI_D4{slash}ETH_RMII_TX_EN{slash}ETH_MII_TX_EN{slash}OTG_HS_SDA{slash}TIM2_CH4-Pad35)") (class "Default")
      (node (ref "PRO_STM32F4DISCOVERY") (pin "35") (pinfunction "PB11/I2C2_SDA/USART3_RX/OTG_HS_ULPI_D4/ETH_RMII_TX_EN/ETH_MII_TX_EN/OTG_HS_SDA/TIM2_CH4_35") (pintype "passive+no_connect"))
    )
    (net (code "84") (name "unconnected-(PRO_STM32F4DISCOVERY-PC0{slash}OTG_HS_ULPI_STP{slash}ADC123_IN10-Pad8)") (class "Default")
      (node (ref "PRO_STM32F4DISCOVERY") (pin "8") (pinfunction "PC0/OTG_HS_ULPI_STP/ADC123_IN10_8") (pintype "passive+no_connect"))
    )
    (net (code "85") (name "unconnected-(PRO_STM32F4DISCOVERY-PC5{slash}ETH_RMII_RX_D1{slash}ETH_MII_RX_D1{slash}ADC12_IN15-Pad19)") (class "Default")
      (node (ref "PRO_STM32F4DISCOVERY") (pin "19") (pinfunction "PC5/ETH_RMII_RX_D1/ETH_MII_RX_D1/ADC12_IN15_19") (pintype "passive+no_connect"))
    )
    (net (code "86") (name "unconnected-(PRO_STM32F4DISCOVERY-PC6{slash}I2S2_MCK{slash}TIM8_CH1{slash}SDIO_D6{slash}USART6_TX{slash}DCMI_D0{slash}TIM3_CH1-Pad97)") (class "Default")
      (node (ref "PRO_STM32F4DISCOVERY") (pin "97") (pinfunction "PC6/I2S2_MCK/TIM8_CH1/SDIO_D6/USART6_TX/DCMI_D0/TIM3_CH1_97") (pintype "passive+no_connect"))
    )
    (net (code "87") (name "unconnected-(PRO_STM32F4DISCOVERY-PC7{slash}I2S3_MCK{slash}TIM8_CH2{slash}SDIO_D7{slash}USART6_RX_DCMI_D1{slash}TIM3_CH2-Pad98)") (class "Default")
      (node (ref "PRO_STM32F4DISCOVERY") (pin "98") (pinfunction "PC7/I2S3_MCK/TIM8_CH2/SDIO_D7/USART6_RX_DCMI_D1/TIM3_CH2_98") (pintype "passive+no_connect"))
    )
    (net (code "88") (name "unconnected-(PRO_STM32F4DISCOVERY-PC10{slash}SPI3_SCK{slash}I2S3_CK{slash}UART4_TX{slash}SDIO_D2{slash}DCMI_D8{slash}USART3_TX-Pad87)") (class "Default")
      (node (ref "PRO_STM32F4DISCOVERY") (pin "87") (pinfunction "PC10/SPI3_SCK/I2S3_CK/UART4_TX/SDIO_D2/DCMI_D8/USART3_TX_87") (pintype "passive+no_connect"))
    )
    (net (code "89") (name "unconnected-(PRO_STM32F4DISCOVERY-PC14{slash}OSC32_IN-Pad59)") (class "Default")
      (node (ref "PRO_STM32F4DISCOVERY") (pin "59") (pinfunction "PC14/OSC32_IN_59") (pintype "passive+no_connect"))
    )
    (net (code "90") (name "unconnected-(PRO_STM32F4DISCOVERY-PC15{slash}OSC32_OUT-Pad60)") (class "Default")
      (node (ref "PRO_STM32F4DISCOVERY") (pin "60") (pinfunction "PC15/OSC32_OUT_60") (pintype "passive+no_connect"))
    )
    (net (code "91") (name "unconnected-(PRO_STM32F4DISCOVERY-PD2{slash}TIM3_ETR{slash}UART5_RXSDIO_CMD{slash}DCMI_D11-Pad84)") (class "Default")
      (node (ref "PRO_STM32F4DISCOVERY") (pin "84") (pinfunction "PD2/TIM3_ETR/UART5_RXSDIO_CMD/DCMI_D11_84") (pintype "passive+no_connect"))
    )
    (net (code "92") (name "unconnected-(PRO_STM32F4DISCOVERY-PD3{slash}FSMC_CLK{slash}USART2_CTS-Pad81)") (class "Default")
      (node (ref "PRO_STM32F4DISCOVERY") (pin "81") (pinfunction "PD3/FSMC_CLK/USART2_CTS_81") (pintype "passive+no_connect"))
    )
    (net (code "93") (name "unconnected-(PRO_STM32F4DISCOVERY-PD4{slash}FSMC_NOE{slash}USART2_RTS-Pad82)") (class "Default")
      (node (ref "PRO_STM32F4DISCOVERY") (pin "82") (pinfunction "PD4/FSMC_NOE/USART2_RTS_82") (pintype "passive+no_connect"))
    )
    (net (code "94") (name "unconnected-(PRO_STM32F4DISCOVERY-PD5{slash}FSMC_NWE{slash}USART2_TX-Pad79)") (class "Default")
      (node (ref "PRO_STM32F4DISCOVERY") (pin "79") (pinfunction "PD5/FSMC_NWE/USART2_TX_79") (pintype "passive+no_connect"))
    )
    (net (code "95") (name "unconnected-(PRO_STM32F4DISCOVERY-PD8{slash}FSMC_D13{slash}USART3_TX-Pad40)") (class "Default")
      (node (ref "PRO_STM32F4DISCOVERY") (pin "40") (pinfunction "PD8/FSMC_D13/USART3_TX_40") (pintype "passive+no_connect"))
    )
    (net (code "96") (name "unconnected-(PRO_STM32F4DISCOVERY-PD9{slash}FSMC_D14{slash}USART3_RX-Pad41)") (class "Default")
      (node (ref "PRO_STM32F4DISCOVERY") (pin "41") (pinfunction "PD9/FSMC_D14/USART3_RX_41") (pintype "passive+no_connect"))
    )
    (net (code "97") (name "unconnected-(PRO_STM32F4DISCOVERY-PE0{slash}TIM4_ETR{slash}FSMC_NBL0{slash}DCMI_D2-Pad67)") (class "Default")
      (node (ref "PRO_STM32F4DISCOVERY") (pin "67") (pinfunction "PE0/TIM4_ETR/FSMC_NBL0/DCMI_D2_67") (pintype "passive+no_connect"))
    )
    (net (code "98") (name "unconnected-(PRO_STM32F4DISCOVERY-PE1{slash}FSMC_NBL1{slash}DCMI_D3-Pad68)") (class "Default")
      (node (ref "PRO_STM32F4DISCOVERY") (pin "68") (pinfunction "PE1/FSMC_NBL1/DCMI_D3_68") (pintype "passive+no_connect"))
    )
    (net (code "99") (name "unconnected-(PRO_STM32F4DISCOVERY-PE2{slash}TRACECLK{slash}FSMC_A23{slash}ETH_MII_TXD3-Pad65)") (class "Default")
      (node (ref "PRO_STM32F4DISCOVERY") (pin "65") (pinfunction "PE2/TRACECLK/FSMC_A23/ETH_MII_TXD3_65") (pintype "passive+no_connect"))
    )
    (net (code "100") (name "unconnected-(PRO_STM32F4DISCOVERY-PE3{slash}TRACED0{slash}FSMC_A19-Pad66)") (class "Default")
      (node (ref "PRO_STM32F4DISCOVERY") (pin "66") (pinfunction "PE3/TRACED0/FSMC_A19_66") (pintype "passive+no_connect"))
    )
    (net (code "101") (name "unconnected-(PRO_STM32F4DISCOVERY-PE4{slash}TRACED1{slash}FSMC_A20{slash}DCMI_D4-Pad63)") (class "Default")
      (node (ref "PRO_STM32F4DISCOVERY") (pin "63") (pinfunction "PE4/TRACED1/FSMC_A20/DCMI_D4_63") (pintype "passive+no_connect"))
    )
    (net (code "102") (name "unconnected-(PRO_STM32F4DISCOVERY-PE5{slash}TRACED2{slash}FSMC_A21{slash}TIM9_CH1{slash}DCMI_D6-Pad64)") (class "Default")
      (node (ref "PRO_STM32F4DISCOVERY") (pin "64") (pinfunction "PE5/TRACED2/FSMC_A21/TIM9_CH1/DCMI_D6_64") (pintype "passive+no_connect"))
    )
    (net (code "103") (name "unconnected-(PRO_STM32F4DISCOVERY-PE6{slash}TRACED3{slash}FSMC_A22{slash}TIM9_CH2{slash}DCMI_D7-Pad61)") (class "Default")
      (node (ref "PRO_STM32F4DISCOVERY") (pin "61") (pinfunction "PE6/TRACED3/FSMC_A22/TIM9_CH2/DCMI_D7_61") (pintype "passive+no_connect"))
    )
    (net (code "104") (name "unconnected-(PRO_STM32F4DISCOVERY-PE7{slash}FSMC_D4{slash}TIM1_ETR-Pad25)") (class "Default")
      (node (ref "PRO_STM32F4DISCOVERY") (pin "25") (pinfunction "PE7/FSMC_D4/TIM1_ETR_25") (pintype "passive+no_connect"))
    )
    (net (code "105") (name "unconnected-(PRO_STM32F4DISCOVERY-PE8{slash}FSMC_D5{slash}TIM1_CH1N-Pad26)") (class "Default")
      (node (ref "PRO_STM32F4DISCOVERY") (pin "26") (pinfunction "PE8/FSMC_D5/TIM1_CH1N_26") (pintype "passive+no_connect"))
    )
    (net (code "106") (name "unconnected-(PRO_STM32F4DISCOVERY-PH0{slash}OSC_IN-Pad57)") (class "Default")
      (node (ref "PRO_STM32F4DISCOVERY") (pin "57") (pinfunction "PH0/OSC_IN_57") (pintype "passive+no_connect"))
    )
    (net (code "107") (name "unconnected-(PRO_STM32F4DISCOVERY-PH1{slash}OSC_OUT-Pad58)") (class "Default")
      (node (ref "PRO_STM32F4DISCOVERY") (pin "58") (pinfunction "PH1/OSC_OUT_58") (pintype "passive+no_connect"))
    )
    (net (code "108") (name "unconnected-(PRO_STM32F4DISCOVERY-VDD-Pad3)") (class "Default")
      (node (ref "PRO_STM32F4DISCOVERY") (pin "3") (pinfunction "VDD_3") (pintype "passive+no_connect"))
    )
    (net (code "109") (name "unconnected-(PRO_STM32F4DISCOVERY-VDD-Pad4)") (class "Default")
      (node (ref "PRO_STM32F4DISCOVERY") (pin "4") (pinfunction "VDD_4") (pintype "passive+no_connect"))
    )
    (net (code "110") (name "unconnected-(PRO_STM32F4DISCOVERY-VDD-Pad72)") (class "Default")
      (node (ref "PRO_STM32F4DISCOVERY") (pin "72") (pinfunction "VDD_72") (pintype "passive+no_connect"))
    )
    (net (code "111") (name "unconnected-(PRO_Ucan-VREF-Pad5)") (class "Default")
      (node (ref "PRO_Ucan") (pin "5") (pinfunction "VREF_5") (pintype "output+no_connect"))
    )
  )
)
